# TeensyChopper.net
KiCad netlist of a schematic drawn in EAGLE
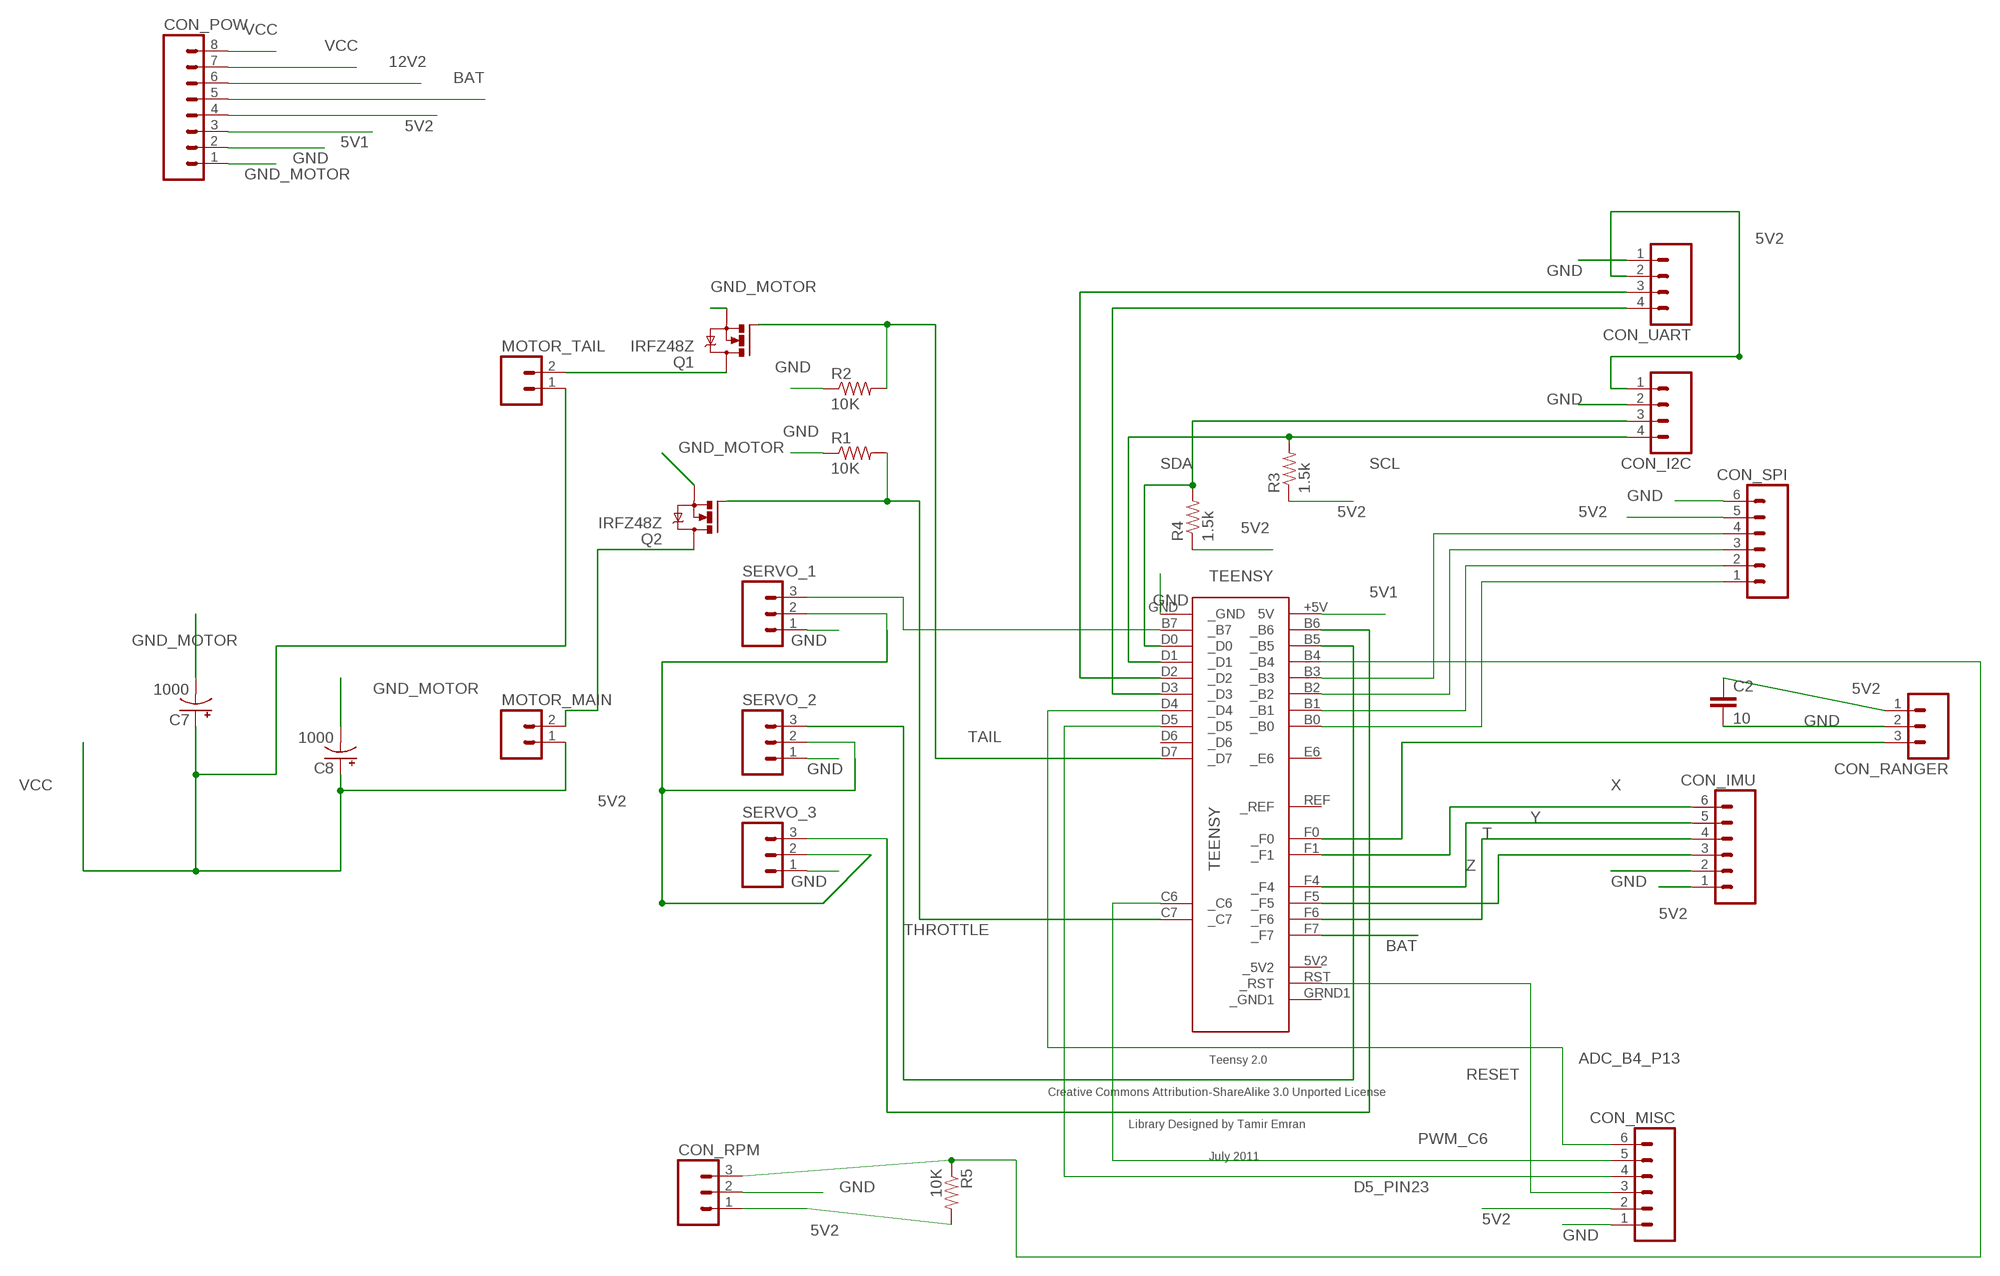
[diagram p0: schematic, sheet 1]

(export (version "E")
  (design (tool "Eeschema 10.0.6"))
  (components
    (comp (ref "C2")
      (value "10")
      (footprint "eagle-import:CAP-PTH-SMALL-KIT")
      (libsource (lib "eagle-import") (part "CAPKIT"))
    )
    (comp (ref "C7")
      (value "1000")
      (footprint "eagle-import:CPOL-RADIAL-1000UF-25V")
      (libsource (lib "eagle-import") (part "CAP_POLPTH4"))
    )
    (comp (ref "C8")
      (value "1000")
      (footprint "eagle-import:CPOL-RADIAL-1000UF-25V")
      (libsource (lib "eagle-import") (part "CAP_POLPTH4"))
    )
    (comp (ref "CON_I2C")
      (value "M04PTH")
      (footprint "eagle-import:1X04")
      (libsource (lib "eagle-import") (part "M04PTH"))
    )
    (comp (ref "CON_IMU")
      (value "M06LOCK")
      (footprint "eagle-import:1X06_LOCK")
      (libsource (lib "eagle-import") (part "M06LOCK"))
    )
    (comp (ref "CON_MISC")
      (value "M06LOCK")
      (footprint "eagle-import:1X06_LOCK")
      (libsource (lib "eagle-import") (part "M06LOCK"))
    )
    (comp (ref "CON_POW")
      (value "M081X08")
      (footprint "eagle-import:1X08")
      (libsource (lib "eagle-import") (part "M081X08"))
    )
    (comp (ref "CON_RANGER")
      (value "M03PTH")
      (footprint "eagle-import:1X03")
      (libsource (lib "eagle-import") (part "M03PTH"))
    )
    (comp (ref "CON_RPM")
      (value "M03PTH")
      (footprint "eagle-import:1X03")
      (libsource (lib "eagle-import") (part "M03PTH"))
    )
    (comp (ref "CON_SPI")
      (value "M06LOCK")
      (footprint "eagle-import:1X06_LOCK")
      (libsource (lib "eagle-import") (part "M06LOCK"))
    )
    (comp (ref "CON_UART")
      (value "M04PTH")
      (footprint "eagle-import:1X04")
      (libsource (lib "eagle-import") (part "M04PTH"))
    )
    (comp (ref "MOTOR_MAIN")
      (value "M025MM")
      (footprint "eagle-import:SCREWTERMINAL-5MM-2")
      (libsource (lib "eagle-import") (part "M025MM"))
    )
    (comp (ref "MOTOR_TAIL")
      (value "M025MM")
      (footprint "eagle-import:SCREWTERMINAL-5MM-2")
      (libsource (lib "eagle-import") (part "M025MM"))
    )
    (comp (ref "Q1")
      (value "IRFZ48Z")
      (footprint "eagle-import:TO220BH")
      (libsource (lib "eagle-import") (part "IRFZ48Z"))
    )
    (comp (ref "Q2")
      (value "IRFZ48Z")
      (footprint "eagle-import:TO220BH")
      (libsource (lib "eagle-import") (part "IRFZ48Z"))
    )
    (comp (ref "R1")
      (value "10K")
      (footprint "eagle-import:AXIAL-0.4")
      (libsource (lib "eagle-import") (part "SparkFun-Resistors_RESISTORPTH-1/4W"))
    )
    (comp (ref "R2")
      (value "10K")
      (footprint "eagle-import:AXIAL-0.4")
      (libsource (lib "eagle-import") (part "SparkFun-Resistors_RESISTORPTH-1/4W"))
    )
    (comp (ref "R3")
      (value "1.5k")
      (footprint "eagle-import:AXIAL-0.4")
      (libsource (lib "eagle-import") (part "RESISTORPTH-1/4W"))
    )
    (comp (ref "R4")
      (value "1.5k")
      (footprint "eagle-import:AXIAL-0.4")
      (libsource (lib "eagle-import") (part "RESISTORPTH-1/4W"))
    )
    (comp (ref "R5")
      (value "10K")
      (footprint "eagle-import:AXIAL-0.4")
      (libsource (lib "eagle-import") (part "SparkFun-Resistors_RESISTORPTH-1/4W"))
    )
    (comp (ref "SERVO_1")
      (value "M03PTH")
      (footprint "eagle-import:1X03")
      (libsource (lib "eagle-import") (part "M03PTH"))
    )
    (comp (ref "SERVO_2")
      (value "M03PTH")
      (footprint "eagle-import:1X03")
      (libsource (lib "eagle-import") (part "M03PTH"))
    )
    (comp (ref "SERVO_3")
      (value "M03PTH")
      (footprint "eagle-import:1X03")
      (libsource (lib "eagle-import") (part "M03PTH"))
    )
    (comp (ref "TEENSY")
      (value "TEENSY")
      (footprint "eagle-import:TEENSY")
      (libsource (lib "eagle-import") (part "TEENSY"))
    )
  )
  (nets
    (net (code "1") (name "/5V1") (class "Default")
      (node (ref "CON_POW") (pin "3") (pinfunction "3_3") (pintype "passive"))
      (node (ref "TEENSY") (pin "+5V") (pinfunction "5V_+5V") (pintype "bidirectional"))
    )
    (net (code "2") (name "/5V2") (class "Default")
      (node (ref "C2") (pin "1") (pinfunction "1_1") (pintype "passive"))
      (node (ref "CON_I2C") (pin "1") (pinfunction "1_1") (pintype "passive"))
      (node (ref "CON_IMU") (pin "1") (pinfunction "1_1") (pintype "passive"))
      (node (ref "CON_MISC") (pin "2") (pinfunction "2_2") (pintype "passive"))
      (node (ref "CON_POW") (pin "4") (pinfunction "4_4") (pintype "passive"))
      (node (ref "CON_RANGER") (pin "1") (pinfunction "1_1") (pintype "passive"))
      (node (ref "CON_RPM") (pin "1") (pinfunction "1_1") (pintype "passive"))
      (node (ref "CON_SPI") (pin "5") (pinfunction "5_5") (pintype "passive"))
      (node (ref "CON_UART") (pin "2") (pinfunction "2_2") (pintype "passive"))
      (node (ref "R3") (pin "P$1") (pinfunction "1_P$1") (pintype "passive"))
      (node (ref "R4") (pin "P$1") (pinfunction "1_P$1") (pintype "passive"))
      (node (ref "R5") (pin "P$2") (pinfunction "2_P$2") (pintype "passive"))
      (node (ref "SERVO_1") (pin "2") (pinfunction "2_2") (pintype "passive"))
      (node (ref "SERVO_2") (pin "2") (pinfunction "2_2") (pintype "passive"))
      (node (ref "SERVO_3") (pin "2") (pinfunction "2_2") (pintype "passive"))
    )
    (net (code "3") (name "/12V2") (class "Default")
      (node (ref "CON_POW") (pin "6") (pinfunction "6_6") (pintype "passive"))
    )
    (net (code "4") (name "/ADC_B4_P13") (class "Default")
      (node (ref "CON_MISC") (pin "6") (pinfunction "6_6") (pintype "passive"))
      (node (ref "TEENSY") (pin "D4") (pinfunction "_D4_D4") (pintype "bidirectional"))
    )
    (net (code "5") (name "/BAT") (class "Default")
      (node (ref "CON_POW") (pin "5") (pinfunction "5_5") (pintype "passive"))
      (node (ref "TEENSY") (pin "F7") (pinfunction "_F7_F7") (pintype "bidirectional"))
    )
    (net (code "6") (name "/D5_PIN23") (class "Default")
      (node (ref "CON_MISC") (pin "4") (pinfunction "4_4") (pintype "passive"))
      (node (ref "TEENSY") (pin "D5") (pinfunction "_D5_D5") (pintype "bidirectional"))
    )
    (net (code "7") (name "/GND") (class "Default")
      (node (ref "C2") (pin "2") (pinfunction "2_2") (pintype "passive"))
      (node (ref "CON_I2C") (pin "2") (pinfunction "2_2") (pintype "passive"))
      (node (ref "CON_IMU") (pin "2") (pinfunction "2_2") (pintype "passive"))
      (node (ref "CON_MISC") (pin "1") (pinfunction "1_1") (pintype "passive"))
      (node (ref "CON_POW") (pin "2") (pinfunction "2_2") (pintype "passive"))
      (node (ref "CON_RANGER") (pin "2") (pinfunction "2_2") (pintype "passive"))
      (node (ref "CON_RPM") (pin "2") (pinfunction "2_2") (pintype "passive"))
      (node (ref "CON_SPI") (pin "6") (pinfunction "6_6") (pintype "passive"))
      (node (ref "CON_UART") (pin "1") (pinfunction "1_1") (pintype "passive"))
      (node (ref "R1") (pin "P$1") (pinfunction "1_P$1") (pintype "passive"))
      (node (ref "R2") (pin "P$1") (pinfunction "1_P$1") (pintype "passive"))
      (node (ref "SERVO_1") (pin "1") (pinfunction "1_1") (pintype "passive"))
      (node (ref "SERVO_2") (pin "1") (pinfunction "1_1") (pintype "passive"))
      (node (ref "SERVO_3") (pin "1") (pinfunction "1_1") (pintype "passive"))
      (node (ref "TEENSY") (pin "GND") (pinfunction "_GND_GND") (pintype "bidirectional"))
    )
    (net (code "8") (name "/GND_MOTOR") (class "Default")
      (node (ref "C7") (pin "2") (pinfunction "-_2") (pintype "passive"))
      (node (ref "C8") (pin "2") (pinfunction "-_2") (pintype "passive"))
      (node (ref "CON_POW") (pin "1") (pinfunction "1_1") (pintype "passive"))
      (node (ref "Q1") (pin "S") (pinfunction "S_S") (pintype "passive"))
      (node (ref "Q2") (pin "S") (pinfunction "S_S") (pintype "passive"))
    )
    (net (code "9") (name "/PWM_C6") (class "Default")
      (node (ref "CON_MISC") (pin "5") (pinfunction "5_5") (pintype "passive"))
      (node (ref "TEENSY") (pin "C6") (pinfunction "_C6_C6") (pintype "bidirectional"))
    )
    (net (code "10") (name "/RESET") (class "Default")
      (node (ref "CON_MISC") (pin "3") (pinfunction "3_3") (pintype "passive"))
      (node (ref "TEENSY") (pin "RST") (pinfunction "_RST_RST") (pintype "bidirectional"))
    )
    (net (code "11") (name "/SCL") (class "Default")
      (node (ref "CON_I2C") (pin "4") (pinfunction "4_4") (pintype "passive"))
      (node (ref "R3") (pin "P$2") (pinfunction "2_P$2") (pintype "passive"))
      (node (ref "TEENSY") (pin "D1") (pinfunction "_D1_D1") (pintype "bidirectional"))
    )
    (net (code "12") (name "/SDA") (class "Default")
      (node (ref "CON_I2C") (pin "3") (pinfunction "3_3") (pintype "passive"))
      (node (ref "R4") (pin "P$2") (pinfunction "2_P$2") (pintype "passive"))
      (node (ref "TEENSY") (pin "D0") (pinfunction "_D0_D0") (pintype "bidirectional"))
    )
    (net (code "13") (name "/T") (class "Default")
      (node (ref "CON_IMU") (pin "4") (pinfunction "4_4") (pintype "passive"))
      (node (ref "TEENSY") (pin "F6") (pinfunction "_F6_F6") (pintype "bidirectional"))
    )
    (net (code "14") (name "/TAIL") (class "Default")
      (node (ref "Q1") (pin "G") (pinfunction "G_G") (pintype "passive"))
      (node (ref "R2") (pin "P$2") (pinfunction "2_P$2") (pintype "passive"))
      (node (ref "TEENSY") (pin "D7") (pinfunction "_D7_D7") (pintype "bidirectional"))
    )
    (net (code "15") (name "/THROTTLE") (class "Default")
      (node (ref "Q2") (pin "G") (pinfunction "G_G") (pintype "passive"))
      (node (ref "R1") (pin "P$2") (pinfunction "2_P$2") (pintype "passive"))
      (node (ref "TEENSY") (pin "C7") (pinfunction "_C7_C7") (pintype "bidirectional"))
    )
    (net (code "16") (name "/VCC") (class "Default")
      (node (ref "C7") (pin "1") (pinfunction "+_1") (pintype "passive"))
      (node (ref "C8") (pin "1") (pinfunction "+_1") (pintype "passive"))
      (node (ref "CON_POW") (pin "7") (pinfunction "7_7") (pintype "passive"))
      (node (ref "CON_POW") (pin "8") (pinfunction "8_8") (pintype "passive"))
      (node (ref "MOTOR_MAIN") (pin "1") (pinfunction "1_1") (pintype "passive"))
      (node (ref "MOTOR_TAIL") (pin "1") (pinfunction "1_1") (pintype "passive"))
    )
    (net (code "17") (name "/X") (class "Default")
      (node (ref "CON_IMU") (pin "6") (pinfunction "6_6") (pintype "passive"))
      (node (ref "TEENSY") (pin "F1") (pinfunction "_F1_F1") (pintype "bidirectional"))
    )
    (net (code "18") (name "/Y") (class "Default")
      (node (ref "CON_IMU") (pin "5") (pinfunction "5_5") (pintype "passive"))
      (node (ref "TEENSY") (pin "F4") (pinfunction "_F4_F4") (pintype "bidirectional"))
    )
    (net (code "19") (name "/Z") (class "Default")
      (node (ref "CON_IMU") (pin "3") (pinfunction "3_3") (pintype "passive"))
      (node (ref "TEENSY") (pin "F5") (pinfunction "_F5_F5") (pintype "bidirectional"))
    )
    (net (code "20") (name "Net-(MOTOR_MAIN-Pad2)") (class "Default")
      (node (ref "MOTOR_MAIN") (pin "2") (pinfunction "2_2") (pintype "passive"))
      (node (ref "Q2") (pin "D") (pinfunction "D_D") (pintype "passive"))
    )
    (net (code "21") (name "Net-(MOTOR_TAIL-Pad2)") (class "Default")
      (node (ref "MOTOR_TAIL") (pin "2") (pinfunction "2_2") (pintype "passive"))
      (node (ref "Q1") (pin "D") (pinfunction "D_D") (pintype "passive"))
    )
    (net (code "22") (name "Net-(R5-1)") (class "Default")
      (node (ref "CON_RPM") (pin "3") (pinfunction "3_3") (pintype "passive"))
      (node (ref "R5") (pin "P$1") (pinfunction "1_P$1") (pintype "passive"))
      (node (ref "TEENSY") (pin "B4") (pinfunction "_B4_B4") (pintype "bidirectional"))
    )
    (net (code "23") (name "Net-(TEENSY-_B0)") (class "Default")
      (node (ref "CON_SPI") (pin "1") (pinfunction "1_1") (pintype "passive"))
      (node (ref "TEENSY") (pin "B0") (pinfunction "_B0_B0") (pintype "bidirectional"))
    )
    (net (code "24") (name "Net-(TEENSY-_B1)") (class "Default")
      (node (ref "CON_SPI") (pin "2") (pinfunction "2_2") (pintype "passive"))
      (node (ref "TEENSY") (pin "B1") (pinfunction "_B1_B1") (pintype "bidirectional"))
    )
    (net (code "25") (name "Net-(TEENSY-_B2)") (class "Default")
      (node (ref "CON_SPI") (pin "3") (pinfunction "3_3") (pintype "passive"))
      (node (ref "TEENSY") (pin "B2") (pinfunction "_B2_B2") (pintype "bidirectional"))
    )
    (net (code "26") (name "Net-(TEENSY-_B3)") (class "Default")
      (node (ref "CON_SPI") (pin "4") (pinfunction "4_4") (pintype "passive"))
      (node (ref "TEENSY") (pin "B3") (pinfunction "_B3_B3") (pintype "bidirectional"))
    )
    (net (code "27") (name "Net-(TEENSY-_B5)") (class "Default")
      (node (ref "SERVO_2") (pin "3") (pinfunction "3_3") (pintype "passive"))
      (node (ref "TEENSY") (pin "B5") (pinfunction "_B5_B5") (pintype "bidirectional"))
    )
    (net (code "28") (name "Net-(TEENSY-_B6)") (class "Default")
      (node (ref "SERVO_3") (pin "3") (pinfunction "3_3") (pintype "passive"))
      (node (ref "TEENSY") (pin "B6") (pinfunction "_B6_B6") (pintype "bidirectional"))
    )
    (net (code "29") (name "Net-(TEENSY-_B7)") (class "Default")
      (node (ref "SERVO_1") (pin "3") (pinfunction "3_3") (pintype "passive"))
      (node (ref "TEENSY") (pin "B7") (pinfunction "_B7_B7") (pintype "bidirectional"))
    )
    (net (code "30") (name "Net-(TEENSY-_D2)") (class "Default")
      (node (ref "CON_UART") (pin "3") (pinfunction "3_3") (pintype "passive"))
      (node (ref "TEENSY") (pin "D2") (pinfunction "_D2_D2") (pintype "bidirectional"))
    )
    (net (code "31") (name "Net-(TEENSY-_D3)") (class "Default")
      (node (ref "CON_UART") (pin "4") (pinfunction "4_4") (pintype "passive"))
      (node (ref "TEENSY") (pin "D3") (pinfunction "_D3_D3") (pintype "bidirectional"))
    )
    (net (code "32") (name "Net-(TEENSY-_F0)") (class "Default")
      (node (ref "CON_RANGER") (pin "3") (pinfunction "3_3") (pintype "passive"))
      (node (ref "TEENSY") (pin "F0") (pinfunction "_F0_F0") (pintype "bidirectional"))
    )
    (net (code "33") (name "unconnected-(TEENSY-_5V2-Pad5V2)") (class "Default")
      (node (ref "TEENSY") (pin "5V2") (pinfunction "_5V2_5V2") (pintype "bidirectional"))
    )
    (net (code "34") (name "unconnected-(TEENSY-_D6-PadD6)") (class "Default")
      (node (ref "TEENSY") (pin "D6") (pinfunction "_D6_D6") (pintype "bidirectional"))
    )
    (net (code "35") (name "unconnected-(TEENSY-_E6-PadE6)") (class "Default")
      (node (ref "TEENSY") (pin "E6") (pinfunction "_E6_E6") (pintype "bidirectional"))
    )
    (net (code "36") (name "unconnected-(TEENSY-_GND1-PadGRND1)") (class "Default")
      (node (ref "TEENSY") (pin "GRND1") (pinfunction "_GND1_GRND1") (pintype "bidirectional"))
    )
    (net (code "37") (name "unconnected-(TEENSY-_REF-PadREF)") (class "Default")
      (node (ref "TEENSY") (pin "REF") (pinfunction "_REF_REF") (pintype "bidirectional"))
    )
  )
)
